# Pr_tica-00.net
KiCad netlist of a schematic drawn in EasyEDA
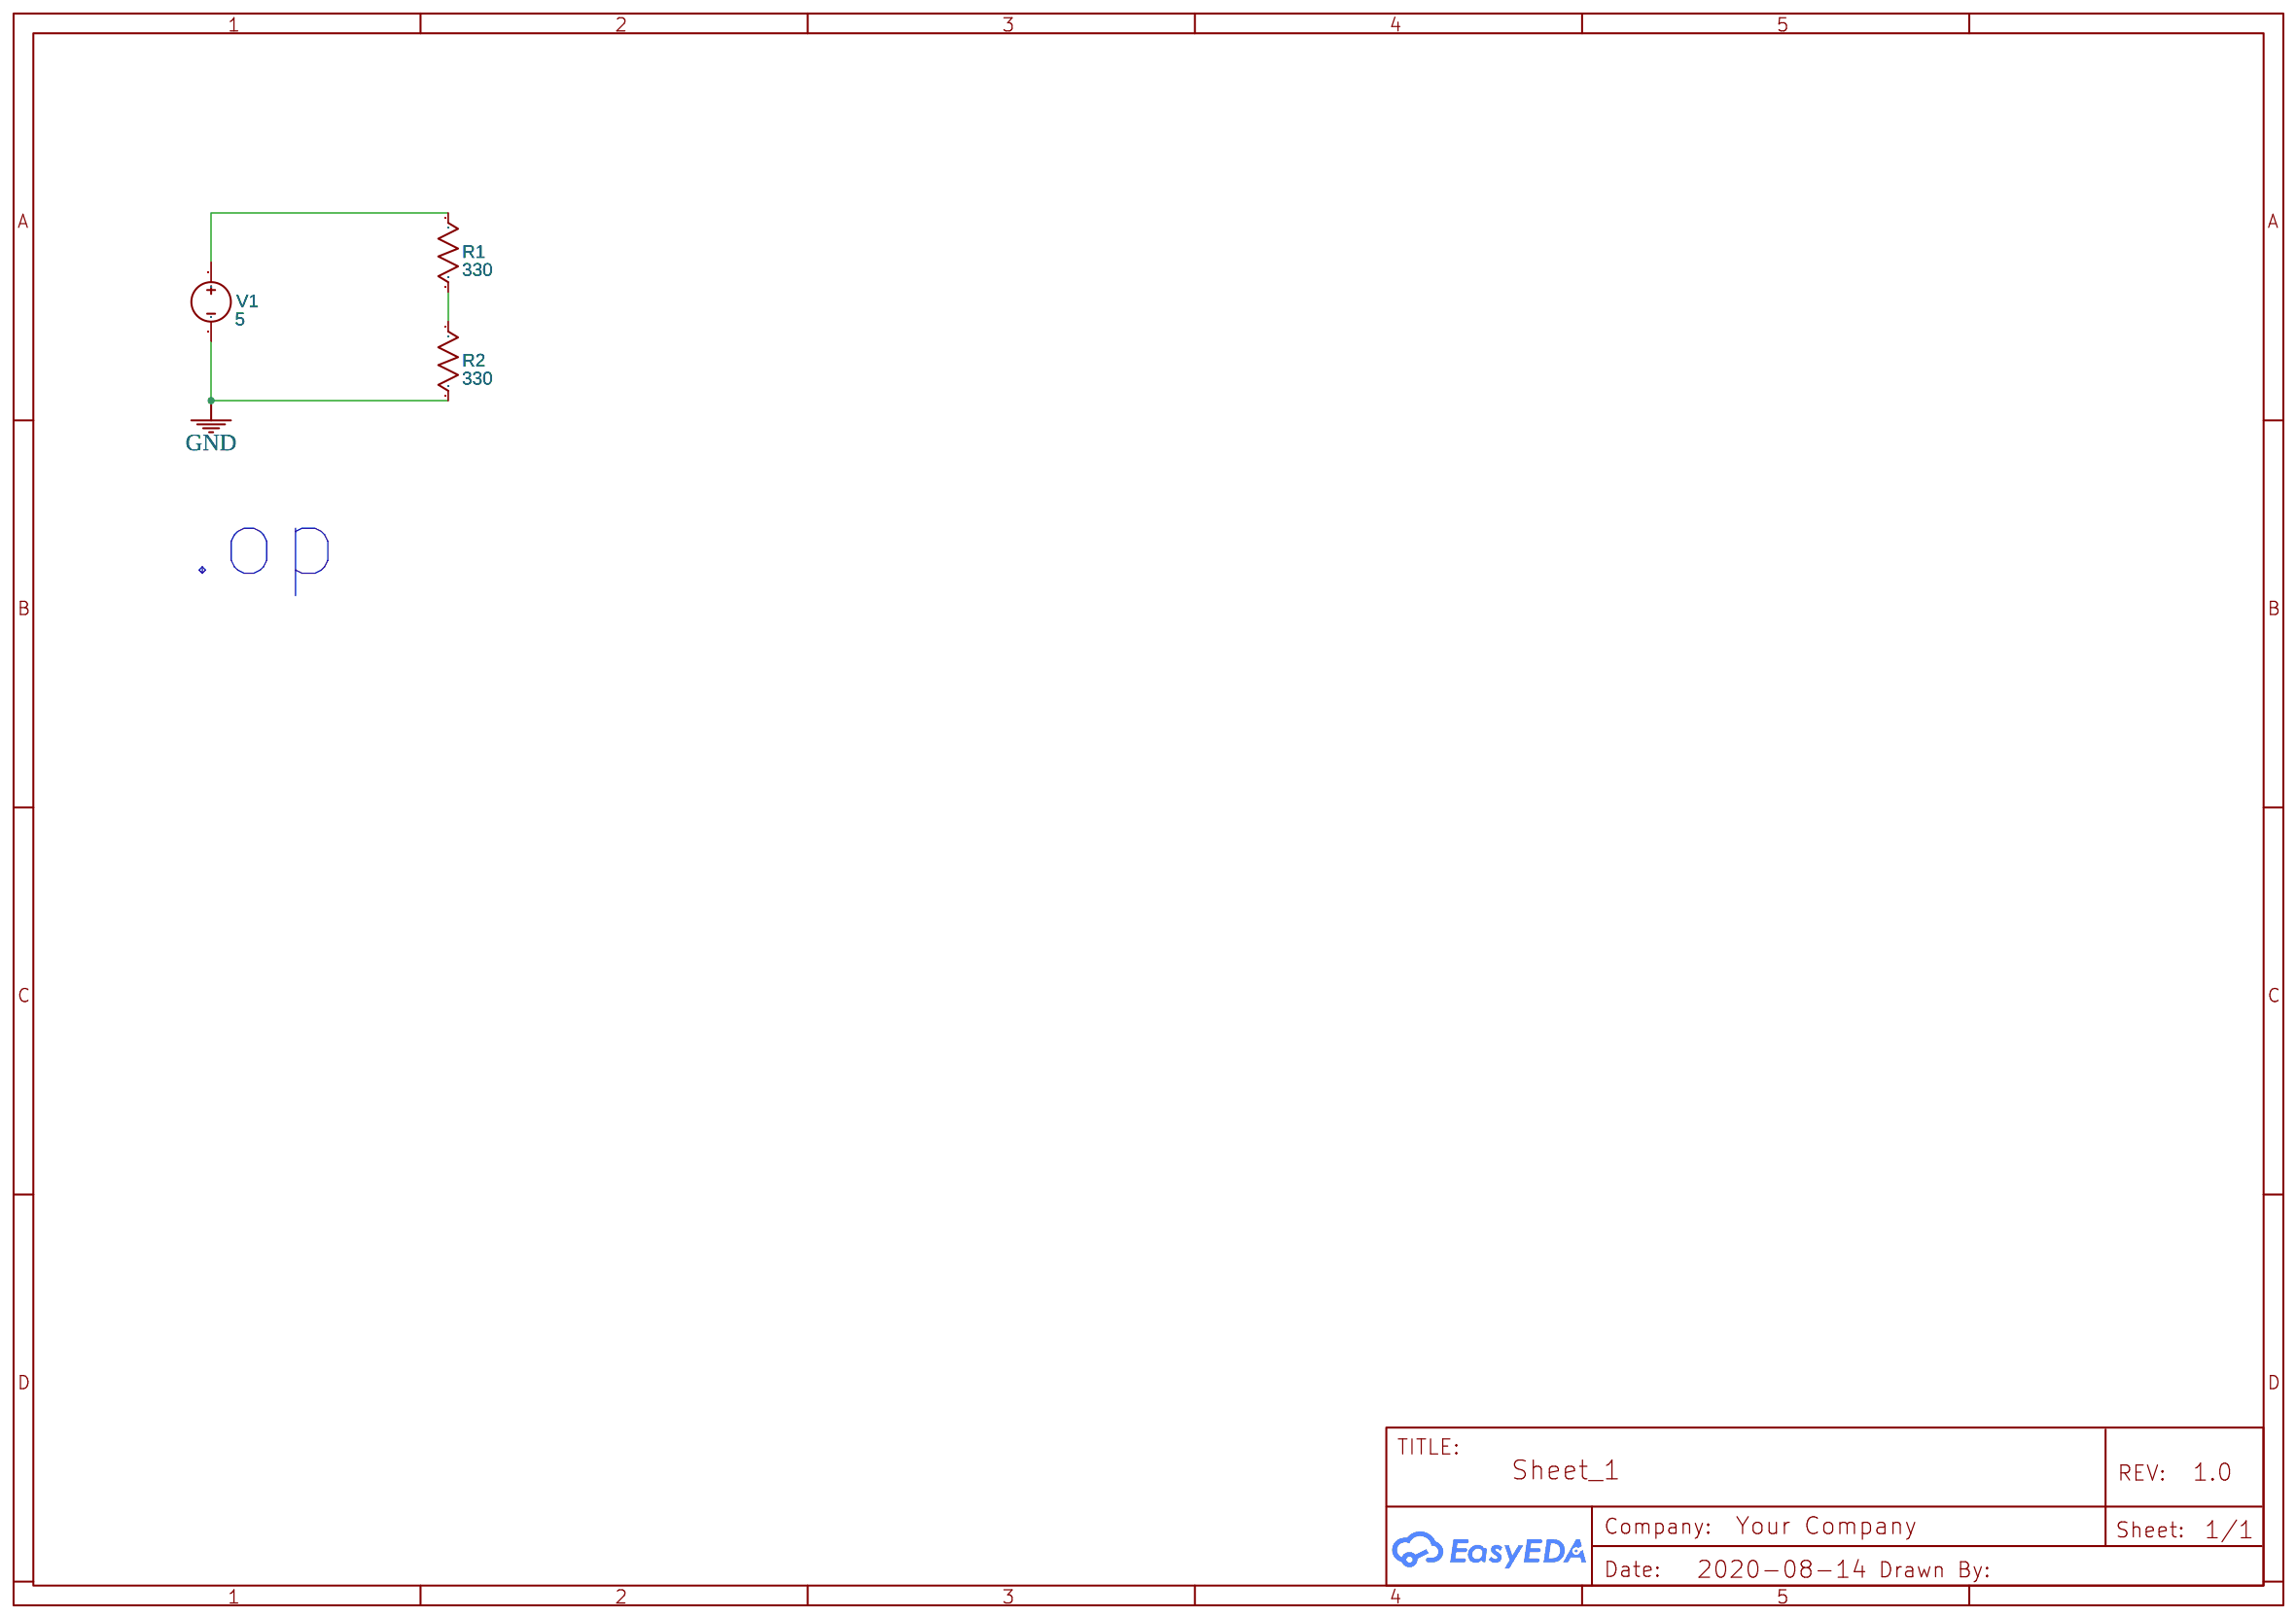
[diagram p0: schematic sheet]

(export (version "E")
  (design (tool "Eeschema 10.0.6"))
  (components
    (comp (ref "R1") (value "330") (libsource (lib "") (part "Resistor_US")))
    (comp (ref "R2") (value "330") (libsource (lib "") (part "Resistor_US")))
    (comp (ref "V1") (value "5") (libsource (lib "") (part "VDC")))
  )
  (nets
    (net (code "1") (name "GND") (class "Default")
      (node (ref "R2") (pin "2") (pinfunction "2_2") (pintype "unspecified"))
      (node (ref "V1") (pin "2") (pinfunction "2_2") (pintype "unspecified"))
    )
    (net (code "2") (name "Net-(R1-Pad1)") (class "Default")
      (node (ref "R1") (pin "1") (pinfunction "1_1") (pintype "unspecified"))
      (node (ref "V1") (pin "1") (pinfunction "1_1") (pintype "unspecified"))
    )
    (net (code "3") (name "Net-(R1-Pad2)") (class "Default")
      (node (ref "R1") (pin "2") (pinfunction "2_2") (pintype "unspecified"))
      (node (ref "R2") (pin "1") (pinfunction "1_1") (pintype "unspecified"))
    )
  )
)
